# Step-Up_DCDC_Converter.net
KiCad netlist of a schematic drawn in Altium Designer
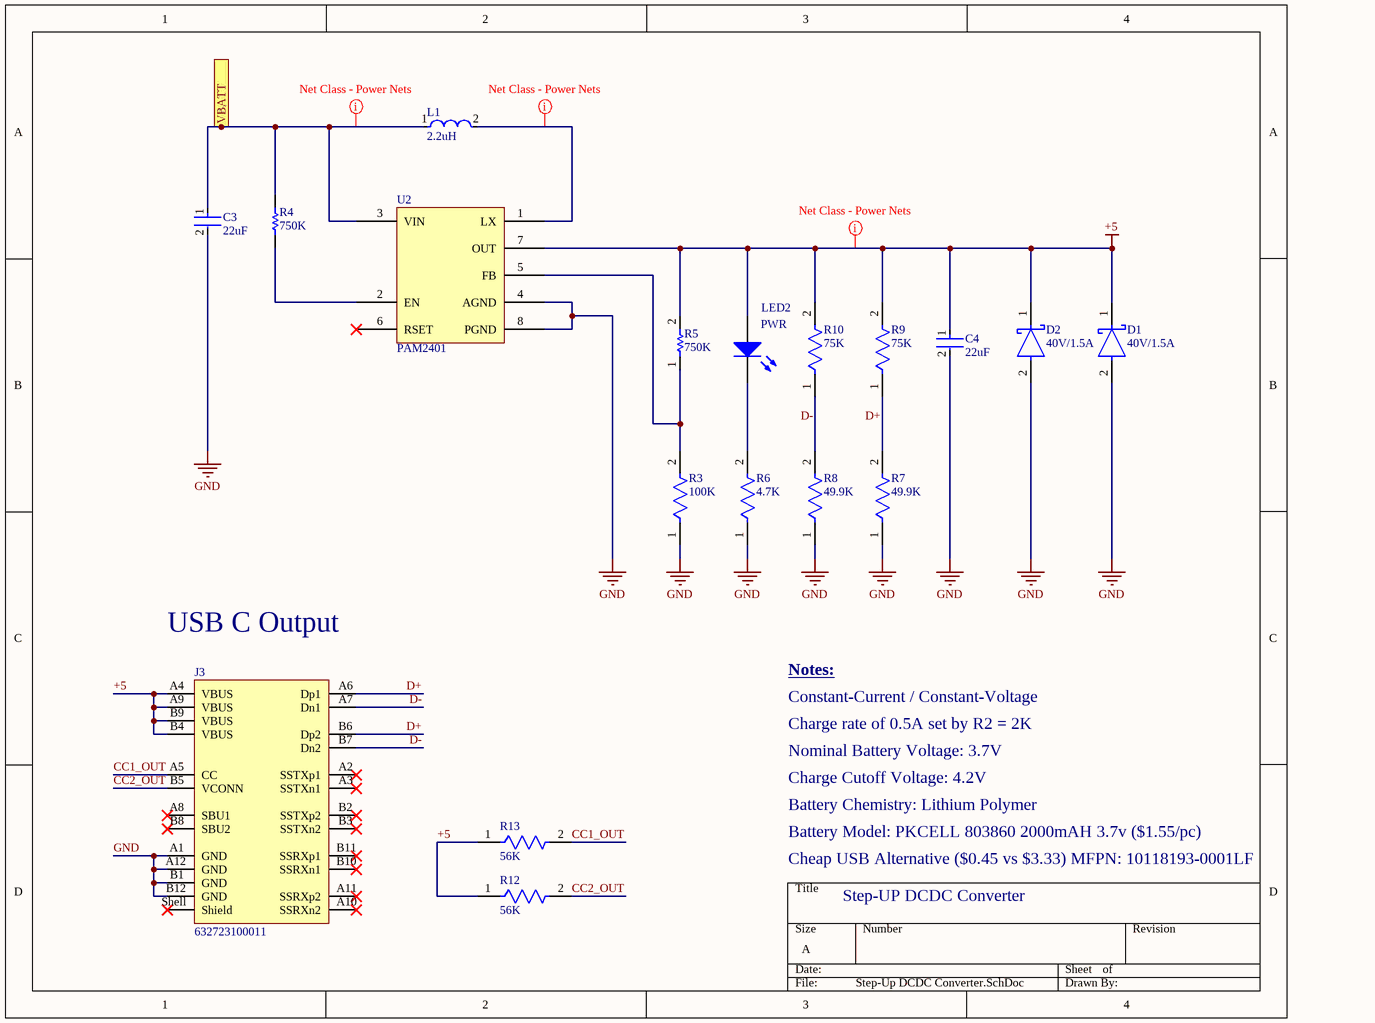
[diagram p0: Step-Up DCDC Converter.SchDoc]

(export (version "E")
  (design (tool "Eeschema 10.0.6"))
  (components
    (comp (ref "C3")
      (value "22uF")
      (footprint "FP-GRM21B-0_15-MFG")
      (description "Chip Multilayer Ceramic Capacitors for General Purpose, 0805, 22uF, X5R, 15%, 20%, 6.3V")
      (fields (field (name "VOLTAGE") "6.3V") (field (name "TOLERANCE") "20%"))
      (libsource (lib "Altium Content Vault") (part "b4654b650e69147ec39a6b967a45e02"))
    )
    (comp (ref "C4")
      (value "22uF")
      (footprint "FP-GRM21B-0_15-MFG")
      (description "Chip Multilayer Ceramic Capacitors for General Purpose, 0805, 22uF, X5R, 15%, 20%, 6.3V")
      (fields (field (name "VOLTAGE") "6.3V") (field (name "TOLERANCE") "20%"))
      (libsource (lib "Altium Content Vault") (part "b4654b650e69147ec39a6b967a45e02"))
    )
    (comp (ref "D1")
      (value "40V/1.5A")
      (footprint "FP-95400-MFG")
      (description "DIODE SCHOTTKY 40V 1.5A SMA")
      (fields
        (field (name "OCTOPART") "https://octopart.com/vs-15mq040ntrpbf-vishay-44340959")
        (field (name "MANUFACTURER") "Vishay")
      )
      (libsource (lib "Altium Content Vault") (part "c1678fac7984e62e0809fbf79c06691"))
    )
    (comp (ref "D2")
      (value "40V/1.5A")
      (footprint "FP-95400-MFG")
      (description "DIODE SCHOTTKY 40V 1.5A SMA")
      (fields
        (field (name "OCTOPART") "https://octopart.com/vs-15mq040ntrpbf-vishay-44340959")
        (field (name "MANUFACTURER") "Vishay")
      )
      (libsource (lib "Altium Content Vault") (part "c1678fac7984e62e0809fbf79c06691"))
    )
    (comp (ref "J3")
      (value "632723100011")
      (footprint "632723100011")
      (description "USB Connector, 24 Contact(s), Female, Right Angle, Solder and Surface Mount Terminal, Receptacle")
      (libsource (lib "Altium Content Vault") (part "USB 3.1_Type C_Receptacle_1 Port"))
    )
    (comp (ref "L1")
      (value "2.2uH")
      (footprint "FP-LQM2HPN_G0-IPC_C")
      (description "Multilayer Type Inductor for Power Lines, 1008 (2520), 2.2μH, 20%, 0.225Ω, 1100mA")
      (fields (field (name "TOLERANCE") "20%"))
      (libsource (lib "Altium Content Vault") (part "725321dda6339637d4d059423bc1c3c"))
    )
    (comp (ref "LED2")
      (value "PWR")
      (footprint "WL-SMCW_0805_150080xx75000")
      (description "Led, Blue, 470 Nm, 3.2 V, 30 Ma, 145 Mcd Rohs Compliant: Yes")
      (libsource (lib "Altium Content Vault") (part "LED_Blue_2A-1K"))
    )
    (comp (ref "R3")
      (value "100K")
      (footprint "FP-CRCW0805-e3-MFG")
      (description "RES Thick Film, 100kΩ, 1%, 0.125W, 100ppm/°C, 0805")
      (fields (field (name "TOLERANCE") "1%"))
      (libsource (lib "Altium Content Vault") (part "1029c3af85768c4190bb7ad29bc67b5"))
    )
    (comp (ref "R4")
      (value "750K")
      (footprint "RESC2013X50X30LL20T20")
      (fields (field (name "MANUFACTURER") "Vishay Dale") (field (name "PART NUMBER") "CRCW0805750KFKEA"))
      (libsource (lib "Altium Content Vault") (part "RES"))
    )
    (comp (ref "R5")
      (value "750K")
      (footprint "RESC2013X50X30LL20T20")
      (fields (field (name "MANUFACTURER") "Vishay Dale") (field (name "PART NUMBER") "CRCW0805750KFKEA"))
      (libsource (lib "") (part "RES_1"))
    )
    (comp (ref "R6")
      (value "4.7K")
      (footprint "FP-CRCW0805-e3-IPC_B")
      (description "RES Thick Film, 4.7kΩ, 1%, 0.125W, 100ppm/°C, 0805")
      (fields (field (name "TOLERANCE") "1%"))
      (libsource (lib "Altium Content Vault") (part "1029c3af85768c4190bb7ad29bc67b5"))
    )
    (comp (ref "R7")
      (value "49.9K")
      (footprint "FP-CRCW0805-e3-IPC_C")
      (description "RES Thick Film, 49.9kΩ, 1%, 0.125W, 100ppm/°C, 0805")
      (fields (field (name "TOLERANCE") "1%"))
      (libsource (lib "Altium Content Vault") (part "1029c3af85768c4190bb7ad29bc67b5"))
    )
    (comp (ref "R8")
      (value "49.9K")
      (footprint "FP-CRCW0805-e3-IPC_C")
      (description "RES Thick Film, 49.9kΩ, 1%, 0.125W, 100ppm/°C, 0805")
      (fields (field (name "TOLERANCE") "1%"))
      (libsource (lib "Altium Content Vault") (part "1029c3af85768c4190bb7ad29bc67b5"))
    )
    (comp (ref "R9")
      (value "75K")
      (footprint "FP-CRCW0805-e3-IPC_A")
      (description "RES Thick Film, 75kΩ, 1%, 0.125W, 100ppm/°C, 0805")
      (fields (field (name "TOLERANCE") "1%"))
      (libsource (lib "Altium Content Vault") (part "1029c3af85768c4190bb7ad29bc67b5"))
    )
    (comp (ref "R10")
      (value "75K")
      (footprint "FP-CRCW0805-e3-IPC_A")
      (description "RES Thick Film, 75kΩ, 1%, 0.125W, 100ppm/°C, 0805")
      (fields (field (name "TOLERANCE") "1%"))
      (libsource (lib "Altium Content Vault") (part "1029c3af85768c4190bb7ad29bc67b5"))
    )
    (comp (ref "R12")
      (value "56K")
      (footprint "FP-CRCW0805-e3-IPC_B")
      (description "RES Thick Film, 56kΩ, 1%, 0.125W, 100ppm/°C, 0805")
      (fields (field (name "TOLERANCE") "1%"))
      (libsource (lib "Altium Content Vault") (part "1029c3af85768c4190bb7ad29bc67b5"))
    )
    (comp (ref "R13")
      (value "56K")
      (footprint "FP-CRCW0805-e3-IPC_B")
      (description "RES Thick Film, 56kΩ, 1%, 0.125W, 100ppm/°C, 0805")
      (fields (field (name "TOLERANCE") "1%"))
      (libsource (lib "Altium Content Vault") (part "1029c3af85768c4190bb7ad29bc67b5"))
    )
    (comp (ref "U2")
      (value "PAM2401")
      (footprint "TSOP65P490X110-8N")
      (description "1.0MHz STEP-UP DC-DC CONVERTER")
      (libsource (lib "CustomLib") (part "PAM2401"))
    )
  )
  (nets
    (net (code "1") (name "+5") (class "Default")
      (node (ref "C4") (pin "1") (pinfunction "1_1") (pintype "passive"))
      (node (ref "D1") (pin "1") (pinfunction "C_1") (pintype "passive"))
      (node (ref "D2") (pin "1") (pinfunction "C_1") (pintype "passive"))
      (node (ref "J3") (pin "A4") (pinfunction "VBUS_A4") (pintype "passive"))
      (node (ref "J3") (pin "A9") (pinfunction "VBUS_A9") (pintype "passive"))
      (node (ref "J3") (pin "B4") (pinfunction "VBUS_B4") (pintype "passive"))
      (node (ref "J3") (pin "B9") (pinfunction "VBUS_B9") (pintype "passive"))
      (node (ref "LED2") (pin "2") (pinfunction "A_2") (pintype "passive"))
      (node (ref "R10") (pin "2") (pinfunction "2_2") (pintype "passive"))
      (node (ref "R12") (pin "1") (pinfunction "1_1") (pintype "passive"))
      (node (ref "R13") (pin "1") (pinfunction "1_1") (pintype "passive"))
      (node (ref "R5") (pin "2") (pinfunction "2_2") (pintype "passive"))
      (node (ref "R9") (pin "2") (pinfunction "2_2") (pintype "passive"))
      (node (ref "U2") (pin "7") (pinfunction "OUT_7") (pintype "passive"))
    )
    (net (code "2") (name "/CC1_OUT") (class "Default")
      (node (ref "J3") (pin "A5") (pinfunction "CC_A5") (pintype "passive"))
      (node (ref "R13") (pin "2") (pinfunction "2_2") (pintype "passive"))
    )
    (net (code "3") (name "/CC2_OUT") (class "Default")
      (node (ref "J3") (pin "B5") (pinfunction "VCONN_B5") (pintype "passive"))
      (node (ref "R12") (pin "2") (pinfunction "2_2") (pintype "passive"))
    )
    (net (code "4") (name "/D+") (class "Default")
      (node (ref "J3") (pin "A6") (pinfunction "Dp1_A6") (pintype "passive"))
      (node (ref "J3") (pin "B6") (pinfunction "Dp2_B6") (pintype "passive"))
      (node (ref "R7") (pin "2") (pinfunction "2_2") (pintype "passive"))
      (node (ref "R9") (pin "1") (pinfunction "1_1") (pintype "passive"))
    )
    (net (code "5") (name "/D-") (class "Default")
      (node (ref "J3") (pin "A7") (pinfunction "Dn1_A7") (pintype "passive"))
      (node (ref "J3") (pin "B7") (pinfunction "Dn2_B7") (pintype "passive"))
      (node (ref "R10") (pin "1") (pinfunction "1_1") (pintype "passive"))
      (node (ref "R8") (pin "2") (pinfunction "2_2") (pintype "passive"))
    )
    (net (code "6") (name "/VBATT") (class "Default")
      (node (ref "C3") (pin "1") (pinfunction "1_1") (pintype "passive"))
      (node (ref "L1") (pin "1") (pinfunction "1_1") (pintype "passive"))
      (node (ref "R4") (pin "2") (pinfunction "2_2") (pintype "passive"))
      (node (ref "U2") (pin "3") (pinfunction "VIN_3") (pintype "passive"))
    )
    (net (code "7") (name "GND") (class "Default")
      (node (ref "C3") (pin "2") (pinfunction "2_2") (pintype "passive"))
      (node (ref "C4") (pin "2") (pinfunction "2_2") (pintype "passive"))
      (node (ref "D1") (pin "2") (pinfunction "A_2") (pintype "passive"))
      (node (ref "D2") (pin "2") (pinfunction "A_2") (pintype "passive"))
      (node (ref "J3") (pin "A1") (pinfunction "GND_A1") (pintype "passive"))
      (node (ref "J3") (pin "A12") (pinfunction "GND_A12") (pintype "passive"))
      (node (ref "J3") (pin "B1") (pinfunction "GND_B1") (pintype "passive"))
      (node (ref "J3") (pin "B12") (pinfunction "GND_B12") (pintype "passive"))
      (node (ref "R3") (pin "1") (pinfunction "1_1") (pintype "passive"))
      (node (ref "R6") (pin "1") (pinfunction "1_1") (pintype "passive"))
      (node (ref "R7") (pin "1") (pinfunction "1_1") (pintype "passive"))
      (node (ref "R8") (pin "1") (pinfunction "1_1") (pintype "passive"))
      (node (ref "U2") (pin "4") (pinfunction "AGND_4") (pintype "passive"))
      (node (ref "U2") (pin "8") (pinfunction "PGND_8") (pintype "passive"))
    )
    (net (code "8") (name "Net-(LED2-K)") (class "Default")
      (node (ref "LED2") (pin "1") (pinfunction "K_1") (pintype "passive"))
      (node (ref "R6") (pin "2") (pinfunction "2_2") (pintype "passive"))
    )
    (net (code "9") (name "Net-(U2-EN)") (class "Default")
      (node (ref "R4") (pin "1") (pinfunction "1_1") (pintype "passive"))
      (node (ref "U2") (pin "2") (pinfunction "EN_2") (pintype "passive"))
    )
    (net (code "10") (name "Net-(U2-FB)") (class "Default")
      (node (ref "R3") (pin "2") (pinfunction "2_2") (pintype "passive"))
      (node (ref "R5") (pin "1") (pinfunction "1_1") (pintype "passive"))
      (node (ref "U2") (pin "5") (pinfunction "FB_5") (pintype "passive"))
    )
    (net (code "11") (name "Net-(U2-LX)") (class "Default")
      (node (ref "L1") (pin "2") (pinfunction "2_2") (pintype "passive"))
      (node (ref "U2") (pin "1") (pinfunction "LX_1") (pintype "passive"))
    )
    (net (code "12") (name "unconnected-(J3-SBU1-PadA8)") (class "Default")
      (node (ref "J3") (pin "A8") (pinfunction "SBU1_A8") (pintype "passive+no_connect"))
    )
    (net (code "13") (name "unconnected-(J3-SBU2-PadB8)") (class "Default")
      (node (ref "J3") (pin "B8") (pinfunction "SBU2_B8") (pintype "passive+no_connect"))
    )
    (net (code "14") (name "unconnected-(J3-SSRXn1-PadB10)") (class "Default")
      (node (ref "J3") (pin "B10") (pinfunction "SSRXn1_B10") (pintype "passive+no_connect"))
    )
    (net (code "15") (name "unconnected-(J3-SSRXn2-PadA10)") (class "Default")
      (node (ref "J3") (pin "A10") (pinfunction "SSRXn2_A10") (pintype "passive+no_connect"))
    )
    (net (code "16") (name "unconnected-(J3-SSRXp1-PadB11)") (class "Default")
      (node (ref "J3") (pin "B11") (pinfunction "SSRXp1_B11") (pintype "passive+no_connect"))
    )
    (net (code "17") (name "unconnected-(J3-SSRXp2-PadA11)") (class "Default")
      (node (ref "J3") (pin "A11") (pinfunction "SSRXp2_A11") (pintype "passive+no_connect"))
    )
    (net (code "18") (name "unconnected-(J3-SSTXn1-PadA3)") (class "Default")
      (node (ref "J3") (pin "A3") (pinfunction "SSTXn1_A3") (pintype "passive+no_connect"))
    )
    (net (code "19") (name "unconnected-(J3-SSTXn2-PadB3)") (class "Default")
      (node (ref "J3") (pin "B3") (pinfunction "SSTXn2_B3") (pintype "passive+no_connect"))
    )
    (net (code "20") (name "unconnected-(J3-SSTXp1-PadA2)") (class "Default")
      (node (ref "J3") (pin "A2") (pinfunction "SSTXp1_A2") (pintype "passive+no_connect"))
    )
    (net (code "21") (name "unconnected-(J3-SSTXp2-PadB2)") (class "Default")
      (node (ref "J3") (pin "B2") (pinfunction "SSTXp2_B2") (pintype "passive+no_connect"))
    )
    (net (code "22") (name "unconnected-(J3-Shield-PadShell)") (class "Default")
      (node (ref "J3") (pin "Shell") (pinfunction "Shield_Shell") (pintype "passive+no_connect"))
    )
    (net (code "23") (name "unconnected-(U2-RSET-Pad6)") (class "Default")
      (node (ref "U2") (pin "6") (pinfunction "RSET_6") (pintype "passive+no_connect"))
    )
  )
)
